# WCS_MK2_v3.net
KiCad netlist of a schematic drawn in EAGLE
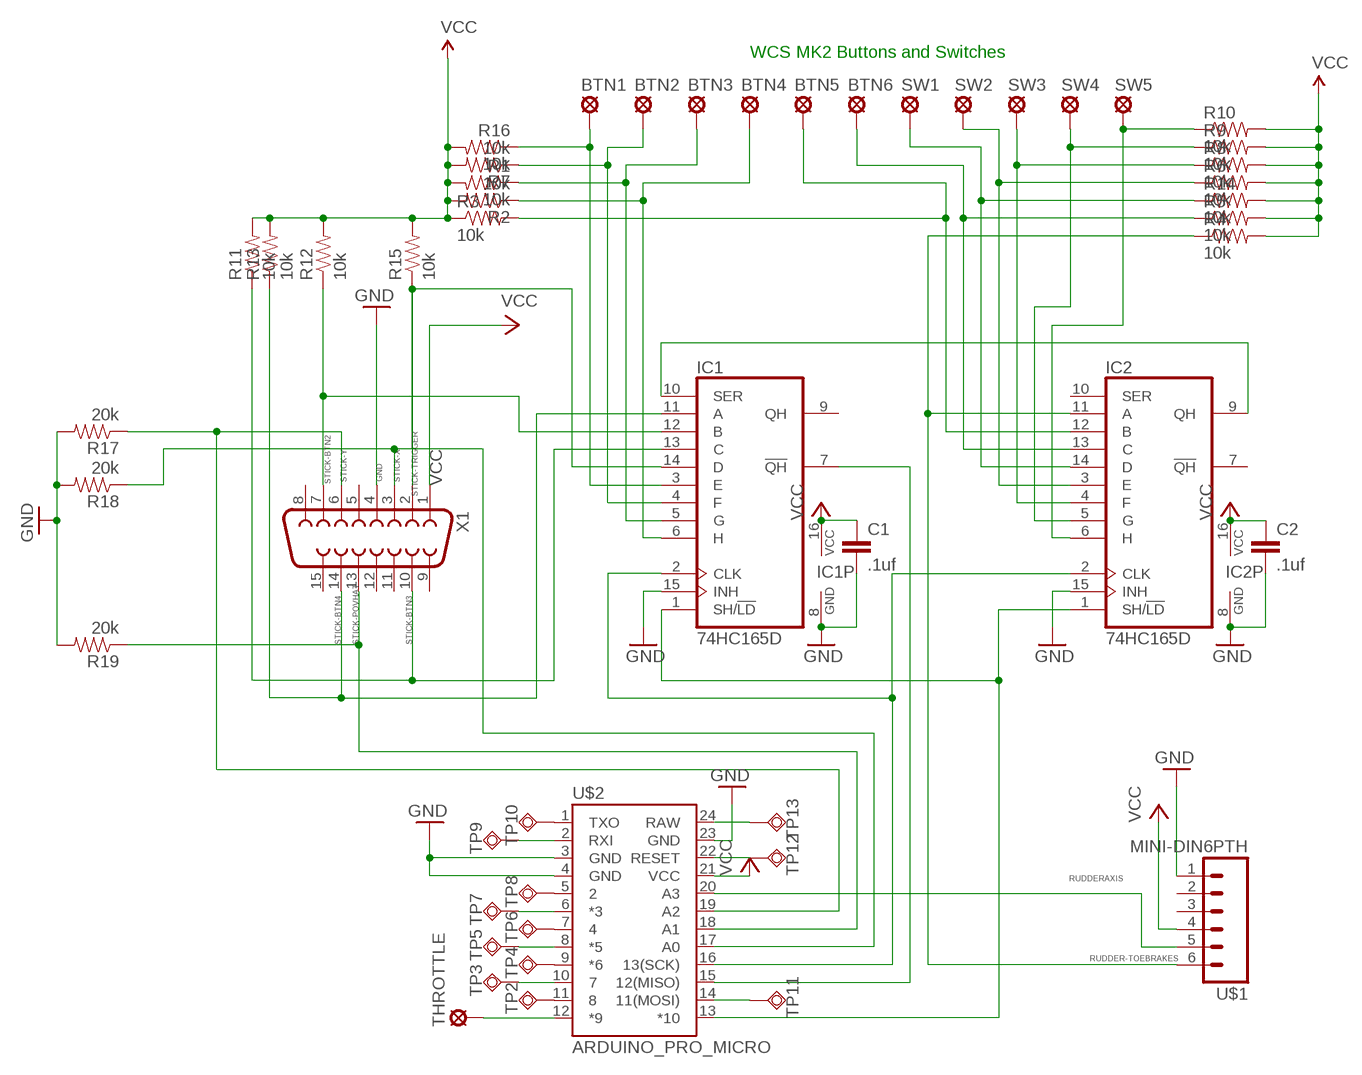
[diagram p0: schematic, sheet 1]

(export (version "E")
  (design (tool "Eeschema 10.0.6"))
  (components
    (comp (ref "BTN1")
      (value "LSP10")
      (footprint "eagle-import:LSP10")
      (libsource (lib "eagle-import") (part "LSP10"))
    )
    (comp (ref "BTN2")
      (value "LSP10")
      (footprint "eagle-import:LSP10")
      (libsource (lib "eagle-import") (part "LSP10"))
    )
    (comp (ref "BTN3")
      (value "LSP10")
      (footprint "eagle-import:LSP10")
      (libsource (lib "eagle-import") (part "LSP10"))
    )
    (comp (ref "BTN4")
      (value "LSP10")
      (footprint "eagle-import:LSP10")
      (libsource (lib "eagle-import") (part "LSP10"))
    )
    (comp (ref "BTN5")
      (value "LSP10")
      (footprint "eagle-import:LSP10")
      (libsource (lib "eagle-import") (part "LSP10"))
    )
    (comp (ref "BTN6")
      (value "LSP10")
      (footprint "eagle-import:LSP10")
      (libsource (lib "eagle-import") (part "LSP10"))
    )
    (comp (ref "C1")
      (value ".1uf")
      (footprint "eagle-import:C025-060X050")
      (libsource (lib "eagle-import") (part "C-EU025-060X050"))
    )
    (comp (ref "C2")
      (value ".1uf")
      (footprint "eagle-import:C025-060X050")
      (libsource (lib "eagle-import") (part "C-EU025-060X050"))
    )
    (comp (ref "IC1")
      (value "74HC165D")
      (footprint "eagle-import:SO16")
      (libsource (lib "eagle-import") (part "74165DHC"))
    )
    (comp (ref "IC2")
      (value "74HC165D")
      (footprint "eagle-import:SO16")
      (libsource (lib "eagle-import") (part "74165DHC"))
    )
    (comp (ref "R1")
      (value "10k")
      (footprint "eagle-import:AXIAL-0.1")
      (libsource (lib "eagle-import") (part "10KOHM-1/4W5%(PTH)VERT"))
    )
    (comp (ref "R2")
      (value "10k")
      (footprint "eagle-import:AXIAL-0.1")
      (libsource (lib "eagle-import") (part "10KOHM-1/4W5%(PTH)VERT"))
    )
    (comp (ref "R3")
      (value "10k")
      (footprint "eagle-import:AXIAL-0.1")
      (libsource (lib "eagle-import") (part "10KOHM-1/4W5%(PTH)VERT"))
    )
    (comp (ref "R4")
      (value "10k")
      (footprint "eagle-import:AXIAL-0.1")
      (libsource (lib "eagle-import") (part "10KOHM-1/4W5%(PTH)VERT"))
    )
    (comp (ref "R5")
      (value "10k")
      (footprint "eagle-import:AXIAL-0.1")
      (libsource (lib "eagle-import") (part "10KOHM-1/4W5%(PTH)VERT"))
    )
    (comp (ref "R6")
      (value "10k")
      (footprint "eagle-import:AXIAL-0.1")
      (libsource (lib "eagle-import") (part "10KOHM-1/4W5%(PTH)VERT"))
    )
    (comp (ref "R7")
      (value "10k")
      (footprint "eagle-import:AXIAL-0.1")
      (libsource (lib "eagle-import") (part "10KOHM-1/4W5%(PTH)VERT"))
    )
    (comp (ref "R8")
      (value "10k")
      (footprint "eagle-import:AXIAL-0.1")
      (libsource (lib "eagle-import") (part "10KOHM-1/4W5%(PTH)VERT"))
    )
    (comp (ref "R9")
      (value "10k")
      (footprint "eagle-import:AXIAL-0.1")
      (libsource (lib "eagle-import") (part "10KOHM-1/4W5%(PTH)VERT"))
    )
    (comp (ref "R10")
      (value "10k")
      (footprint "eagle-import:AXIAL-0.1")
      (libsource (lib "eagle-import") (part "10KOHM-1/4W5%(PTH)VERT"))
    )
    (comp (ref "R11")
      (value "10k")
      (footprint "eagle-import:AXIAL-0.1")
      (libsource (lib "eagle-import") (part "10KOHM-1/4W5%(PTH)VERT"))
    )
    (comp (ref "R12")
      (value "10k")
      (footprint "eagle-import:AXIAL-0.1")
      (libsource (lib "eagle-import") (part "10KOHM-1/4W5%(PTH)VERT"))
    )
    (comp (ref "R13")
      (value "10k")
      (footprint "eagle-import:AXIAL-0.1")
      (libsource (lib "eagle-import") (part "10KOHM-1/4W5%(PTH)VERT"))
    )
    (comp (ref "R14")
      (value "10k")
      (footprint "eagle-import:AXIAL-0.1")
      (libsource (lib "eagle-import") (part "10KOHM-1/4W5%(PTH)VERT"))
    )
    (comp (ref "R15")
      (value "10k")
      (footprint "eagle-import:AXIAL-0.1")
      (libsource (lib "eagle-import") (part "10KOHM-1/4W5%(PTH)VERT"))
    )
    (comp (ref "R16")
      (value "10k")
      (footprint "eagle-import:AXIAL-0.1")
      (libsource (lib "eagle-import") (part "10KOHM-1/4W5%(PTH)VERT"))
    )
    (comp (ref "R17")
      (value "20k")
      (footprint "eagle-import:AXIAL-0.1")
      (libsource (lib "eagle-import") (part "10KOHM-1/4W5%(PTH)VERT"))
    )
    (comp (ref "R18")
      (value "20k")
      (footprint "eagle-import:AXIAL-0.1")
      (libsource (lib "eagle-import") (part "10KOHM-1/4W5%(PTH)VERT"))
    )
    (comp (ref "R19")
      (value "20k")
      (footprint "eagle-import:AXIAL-0.1")
      (libsource (lib "eagle-import") (part "10KOHM-1/4W5%(PTH)VERT"))
    )
    (comp (ref "SW1")
      (value "LSP10")
      (footprint "eagle-import:LSP10")
      (libsource (lib "eagle-import") (part "LSP10"))
    )
    (comp (ref "SW2")
      (value "LSP10")
      (footprint "eagle-import:LSP10")
      (libsource (lib "eagle-import") (part "LSP10"))
    )
    (comp (ref "SW3")
      (value "LSP10")
      (footprint "eagle-import:LSP10")
      (libsource (lib "eagle-import") (part "LSP10"))
    )
    (comp (ref "SW4")
      (value "LSP10")
      (footprint "eagle-import:LSP10")
      (libsource (lib "eagle-import") (part "LSP10"))
    )
    (comp (ref "SW5")
      (value "LSP10")
      (footprint "eagle-import:LSP10")
      (libsource (lib "eagle-import") (part "LSP10"))
    )
    (comp (ref "THROTTLE")
      (value "LSP10")
      (footprint "eagle-import:LSP10")
      (libsource (lib "eagle-import") (part "LSP10"))
    )
    (comp (ref "TP2")
      (value "TPSQTP20SQ")
      (footprint "eagle-import:TP20SQ")
      (libsource (lib "eagle-import") (part "TPSQTP20SQ"))
    )
    (comp (ref "TP3")
      (value "TPSQTP20SQ")
      (footprint "eagle-import:TP20SQ")
      (libsource (lib "eagle-import") (part "TPSQTP20SQ"))
    )
    (comp (ref "TP4")
      (value "TPSQTP20SQ")
      (footprint "eagle-import:TP20SQ")
      (libsource (lib "eagle-import") (part "TPSQTP20SQ"))
    )
    (comp (ref "TP5")
      (value "TPSQTP20SQ")
      (footprint "eagle-import:TP20SQ")
      (libsource (lib "eagle-import") (part "TPSQTP20SQ"))
    )
    (comp (ref "TP6")
      (value "TPSQTP20SQ")
      (footprint "eagle-import:TP20SQ")
      (libsource (lib "eagle-import") (part "TPSQTP20SQ"))
    )
    (comp (ref "TP7")
      (value "TPSQTP20SQ")
      (footprint "eagle-import:TP20SQ")
      (libsource (lib "eagle-import") (part "TPSQTP20SQ"))
    )
    (comp (ref "TP8")
      (value "TPSQTP20SQ")
      (footprint "eagle-import:TP20SQ")
      (libsource (lib "eagle-import") (part "TPSQTP20SQ"))
    )
    (comp (ref "TP9")
      (value "TPSQTP20SQ")
      (footprint "eagle-import:TP20SQ")
      (libsource (lib "eagle-import") (part "TPSQTP20SQ"))
    )
    (comp (ref "TP10")
      (value "TPSQTP20SQ")
      (footprint "eagle-import:TP20SQ")
      (libsource (lib "eagle-import") (part "TPSQTP20SQ"))
    )
    (comp (ref "TP11")
      (value "TPSQTP20SQ")
      (footprint "eagle-import:TP20SQ")
      (libsource (lib "eagle-import") (part "TPSQTP20SQ"))
    )
    (comp (ref "TP12")
      (value "TPSQTP20SQ")
      (footprint "eagle-import:TP20SQ")
      (libsource (lib "eagle-import") (part "TPSQTP20SQ"))
    )
    (comp (ref "TP13")
      (value "TPSQTP20SQ")
      (footprint "eagle-import:TP20SQ")
      (libsource (lib "eagle-import") (part "TPSQTP20SQ"))
    )
    (comp (ref "U$1")
      (value "MINI-DIN6PTH")
      (footprint "eagle-import:MINI-DIN6")
      (libsource (lib "eagle-import") (part "MINI-DIN6PTH"))
    )
    (comp (ref "U$2")
      (value "ARDUINO_PRO_MICRO")
      (footprint "eagle-import:ARDUINO_PRO_MICRO")
      (libsource (lib "eagle-import") (part "ARDUINO_PRO_MICRO"))
    )
    (comp (ref "X1")
      (value "F15HP")
      (footprint "eagle-import:F15HP")
      (libsource (lib "eagle-import") (part "F15HP"))
    )
  )
  (nets
    (net (code "1") (name "/RUDDER-TOEBRAKES") (class "Default")
      (node (ref "IC2") (pin "11") (pinfunction "A_11") (pintype "input"))
      (node (ref "R4") (pin "P$1") (pinfunction "1_P$1") (pintype "passive"))
      (node (ref "U$1") (pin "6") (pinfunction "6_6") (pintype "passive"))
    )
    (net (code "2") (name "/RUDDERAXIS") (class "Default")
      (node (ref "U$1") (pin "5") (pinfunction "5_5") (pintype "passive"))
      (node (ref "U$2") (pin "20") (pinfunction "A3_20") (pintype "bidirectional"))
    )
    (net (code "3") (name "/STICK-BTN2") (class "Default")
      (node (ref "IC1") (pin "12") (pinfunction "B_12") (pintype "input"))
      (node (ref "R12") (pin "P$1") (pinfunction "1_P$1") (pintype "passive"))
      (node (ref "X1") (pin "7") (pinfunction "7_7") (pintype "passive"))
    )
    (net (code "4") (name "/STICK-BTN3") (class "Default")
      (node (ref "IC1") (pin "13") (pinfunction "C_13") (pintype "input"))
      (node (ref "R11") (pin "P$1") (pinfunction "1_P$1") (pintype "passive"))
      (node (ref "X1") (pin "10") (pinfunction "10_10") (pintype "passive"))
    )
    (net (code "5") (name "/STICK-BTN4") (class "Default")
      (node (ref "IC1") (pin "11") (pinfunction "A_11") (pintype "input"))
      (node (ref "R13") (pin "P$1") (pinfunction "1_P$1") (pintype "passive"))
      (node (ref "X1") (pin "14") (pinfunction "14_14") (pintype "passive"))
    )
    (net (code "6") (name "/STICK-POVHAT") (class "Default")
      (node (ref "R19") (pin "P$1") (pinfunction "1_P$1") (pintype "passive"))
      (node (ref "U$2") (pin "18") (pinfunction "A1_18") (pintype "bidirectional"))
      (node (ref "X1") (pin "13") (pinfunction "13_13") (pintype "passive"))
    )
    (net (code "7") (name "/STICK-TRIGGER") (class "Default")
      (node (ref "IC1") (pin "14") (pinfunction "D_14") (pintype "input"))
      (node (ref "R15") (pin "P$1") (pinfunction "1_P$1") (pintype "passive"))
      (node (ref "X1") (pin "2") (pinfunction "2_2") (pintype "passive"))
    )
    (net (code "8") (name "/STICK-X") (class "Default")
      (node (ref "R18") (pin "P$1") (pinfunction "1_P$1") (pintype "passive"))
      (node (ref "U$2") (pin "17") (pinfunction "A0_17") (pintype "bidirectional"))
      (node (ref "X1") (pin "3") (pinfunction "3_3") (pintype "passive"))
    )
    (net (code "9") (name "/STICK-Y") (class "Default")
      (node (ref "R17") (pin "P$1") (pinfunction "1_P$1") (pintype "passive"))
      (node (ref "U$2") (pin "19") (pinfunction "A2_19") (pintype "bidirectional"))
      (node (ref "X1") (pin "6") (pinfunction "6_6") (pintype "passive"))
    )
    (net (code "10") (name "GND") (class "Default")
      (node (ref "C1") (pin "2") (pinfunction "2_2") (pintype "passive"))
      (node (ref "C2") (pin "2") (pinfunction "2_2") (pintype "passive"))
      (node (ref "IC1") (pin "15") (pinfunction "INH_15") (pintype "input"))
      (node (ref "IC1") (pin "8") (pinfunction "GND_8") (pintype "power_in"))
      (node (ref "IC2") (pin "15") (pinfunction "INH_15") (pintype "input"))
      (node (ref "IC2") (pin "8") (pinfunction "GND_8") (pintype "power_in"))
      (node (ref "R17") (pin "P$2") (pinfunction "2_P$2") (pintype "passive"))
      (node (ref "R18") (pin "P$2") (pinfunction "2_P$2") (pintype "passive"))
      (node (ref "R19") (pin "P$2") (pinfunction "2_P$2") (pintype "passive"))
      (node (ref "U$1") (pin "1") (pinfunction "1_1") (pintype "passive"))
      (node (ref "U$2") (pin "23") (pinfunction "GND_23") (pintype "bidirectional"))
      (node (ref "U$2") (pin "3") (pinfunction "GND_3") (pintype "bidirectional"))
      (node (ref "U$2") (pin "4") (pinfunction "GND_4") (pintype "bidirectional"))
      (node (ref "X1") (pin "4") (pinfunction "4_4") (pintype "passive"))
    )
    (net (code "11") (name "Net-(IC1A-CLK)") (class "Default")
      (node (ref "IC1") (pin "2") (pinfunction "CLK_2") (pintype "input"))
      (node (ref "IC2") (pin "2") (pinfunction "CLK_2") (pintype "input"))
      (node (ref "U$2") (pin "16") (pinfunction "13(SCK)_16") (pintype "bidirectional"))
    )
    (net (code "12") (name "Net-(IC1A-E)") (class "Default")
      (node (ref "BTN1") (pin "MP") (pinfunction "MP_MP") (pintype "passive"))
      (node (ref "IC1") (pin "3") (pinfunction "E_3") (pintype "input"))
      (node (ref "R16") (pin "P$1") (pinfunction "1_P$1") (pintype "passive"))
    )
    (net (code "13") (name "Net-(IC1A-F)") (class "Default")
      (node (ref "BTN2") (pin "MP") (pinfunction "MP_MP") (pintype "passive"))
      (node (ref "IC1") (pin "4") (pinfunction "F_4") (pintype "input"))
      (node (ref "R7") (pin "P$1") (pinfunction "1_P$1") (pintype "passive"))
    )
    (net (code "14") (name "Net-(IC1A-G)") (class "Default")
      (node (ref "BTN3") (pin "MP") (pinfunction "MP_MP") (pintype "passive"))
      (node (ref "IC1") (pin "5") (pinfunction "G_5") (pintype "input"))
      (node (ref "R1") (pin "P$1") (pinfunction "1_P$1") (pintype "passive"))
    )
    (net (code "15") (name "Net-(IC1A-H)") (class "Default")
      (node (ref "BTN4") (pin "MP") (pinfunction "MP_MP") (pintype "passive"))
      (node (ref "IC1") (pin "6") (pinfunction "H_6") (pintype "input"))
      (node (ref "R2") (pin "P$1") (pinfunction "1_P$1") (pintype "passive"))
    )
    (net (code "16") (name "Net-(IC1A-SER)") (class "Default")
      (node (ref "IC1") (pin "10") (pinfunction "SER_10") (pintype "input"))
      (node (ref "IC2") (pin "9") (pinfunction "QH_9") (pintype "output"))
    )
    (net (code "17") (name "Net-(IC1A-SH{slash}~{LD})") (class "Default")
      (node (ref "IC1") (pin "1") (pinfunction "SH/~{LD}_1") (pintype "input"))
      (node (ref "IC2") (pin "1") (pinfunction "SH/~{LD}_1") (pintype "input"))
      (node (ref "U$2") (pin "13") (pinfunction "*10_13") (pintype "bidirectional"))
    )
    (net (code "18") (name "Net-(IC1A-~{QH})") (class "Default")
      (node (ref "IC1") (pin "7") (pinfunction "~{QH}_7") (pintype "output"))
      (node (ref "U$2") (pin "15") (pinfunction "12(MISO)_15") (pintype "bidirectional"))
    )
    (net (code "19") (name "Net-(IC2A-B)") (class "Default")
      (node (ref "BTN5") (pin "MP") (pinfunction "MP_MP") (pintype "passive"))
      (node (ref "IC2") (pin "12") (pinfunction "B_12") (pintype "input"))
      (node (ref "R3") (pin "P$2") (pinfunction "2_P$2") (pintype "passive"))
    )
    (net (code "20") (name "Net-(IC2A-C)") (class "Default")
      (node (ref "BTN6") (pin "MP") (pinfunction "MP_MP") (pintype "passive"))
      (node (ref "IC2") (pin "13") (pinfunction "C_13") (pintype "input"))
      (node (ref "R5") (pin "P$1") (pinfunction "1_P$1") (pintype "passive"))
    )
    (net (code "21") (name "Net-(IC2A-D)") (class "Default")
      (node (ref "IC2") (pin "14") (pinfunction "D_14") (pintype "input"))
      (node (ref "R14") (pin "P$1") (pinfunction "1_P$1") (pintype "passive"))
      (node (ref "SW1") (pin "MP") (pinfunction "MP_MP") (pintype "passive"))
    )
    (net (code "22") (name "Net-(IC2A-E)") (class "Default")
      (node (ref "IC2") (pin "3") (pinfunction "E_3") (pintype "input"))
      (node (ref "R6") (pin "P$1") (pinfunction "1_P$1") (pintype "passive"))
      (node (ref "SW2") (pin "MP") (pinfunction "MP_MP") (pintype "passive"))
    )
    (net (code "23") (name "Net-(IC2A-F)") (class "Default")
      (node (ref "IC2") (pin "4") (pinfunction "F_4") (pintype "input"))
      (node (ref "R8") (pin "P$1") (pinfunction "1_P$1") (pintype "passive"))
      (node (ref "SW3") (pin "MP") (pinfunction "MP_MP") (pintype "passive"))
    )
    (net (code "24") (name "Net-(IC2A-G)") (class "Default")
      (node (ref "IC2") (pin "5") (pinfunction "G_5") (pintype "input"))
      (node (ref "R9") (pin "P$1") (pinfunction "1_P$1") (pintype "passive"))
      (node (ref "SW4") (pin "MP") (pinfunction "MP_MP") (pintype "passive"))
    )
    (net (code "25") (name "Net-(IC2A-H)") (class "Default")
      (node (ref "IC2") (pin "6") (pinfunction "H_6") (pintype "input"))
      (node (ref "R10") (pin "P$1") (pinfunction "1_P$1") (pintype "passive"))
      (node (ref "SW5") (pin "MP") (pinfunction "MP_MP") (pintype "passive"))
    )
    (net (code "26") (name "Net-(U$2-*3)") (class "Default")
      (node (ref "TP7") (pin "TP") (pinfunction "TP_TP") (pintype "input"))
      (node (ref "U$2") (pin "6") (pinfunction "*3_6") (pintype "bidirectional"))
    )
    (net (code "27") (name "Net-(U$2-*5)") (class "Default")
      (node (ref "TP5") (pin "TP") (pinfunction "TP_TP") (pintype "input"))
      (node (ref "U$2") (pin "8") (pinfunction "*5_8") (pintype "bidirectional"))
    )
    (net (code "28") (name "Net-(U$2-*6)") (class "Default")
      (node (ref "TP4") (pin "TP") (pinfunction "TP_TP") (pintype "input"))
      (node (ref "U$2") (pin "9") (pinfunction "*6_9") (pintype "bidirectional"))
    )
    (net (code "29") (name "Net-(U$2-*9)") (class "Default")
      (node (ref "THROTTLE") (pin "MP") (pinfunction "MP_MP") (pintype "passive"))
      (node (ref "U$2") (pin "12") (pinfunction "*9_12") (pintype "bidirectional"))
    )
    (net (code "30") (name "Net-(U$2-2)") (class "Default")
      (node (ref "TP8") (pin "TP") (pinfunction "TP_TP") (pintype "input"))
      (node (ref "U$2") (pin "5") (pinfunction "2_5") (pintype "bidirectional"))
    )
    (net (code "31") (name "Net-(U$2-4)") (class "Default")
      (node (ref "TP6") (pin "TP") (pinfunction "TP_TP") (pintype "input"))
      (node (ref "U$2") (pin "7") (pinfunction "4_7") (pintype "bidirectional"))
    )
    (net (code "32") (name "Net-(U$2-7)") (class "Default")
      (node (ref "TP3") (pin "TP") (pinfunction "TP_TP") (pintype "input"))
      (node (ref "U$2") (pin "10") (pinfunction "7_10") (pintype "bidirectional"))
    )
    (net (code "33") (name "Net-(U$2-8)") (class "Default")
      (node (ref "TP2") (pin "TP") (pinfunction "TP_TP") (pintype "input"))
      (node (ref "U$2") (pin "11") (pinfunction "8_11") (pintype "bidirectional"))
    )
    (net (code "34") (name "Net-(U$2-11(MOSI))") (class "Default")
      (node (ref "TP11") (pin "TP") (pinfunction "TP_TP") (pintype "input"))
      (node (ref "U$2") (pin "14") (pinfunction "11(MOSI)_14") (pintype "bidirectional"))
    )
    (net (code "35") (name "Net-(U$2-RAW)") (class "Default")
      (node (ref "TP13") (pin "TP") (pinfunction "TP_TP") (pintype "input"))
      (node (ref "U$2") (pin "24") (pinfunction "RAW_24") (pintype "bidirectional"))
    )
    (net (code "36") (name "Net-(U$2-RESET)") (class "Default")
      (node (ref "TP12") (pin "TP") (pinfunction "TP_TP") (pintype "input"))
      (node (ref "U$2") (pin "22") (pinfunction "RESET_22") (pintype "bidirectional"))
    )
    (net (code "37") (name "Net-(U$2-RXI)") (class "Default")
      (node (ref "TP9") (pin "TP") (pinfunction "TP_TP") (pintype "input"))
      (node (ref "U$2") (pin "2") (pinfunction "RXI_2") (pintype "bidirectional"))
    )
    (net (code "38") (name "Net-(U$2-TXO)") (class "Default")
      (node (ref "TP10") (pin "TP") (pinfunction "TP_TP") (pintype "input"))
      (node (ref "U$2") (pin "1") (pinfunction "TXO_1") (pintype "bidirectional"))
    )
    (net (code "39") (name "VCC") (class "Default")
      (node (ref "C1") (pin "1") (pinfunction "1_1") (pintype "passive"))
      (node (ref "C2") (pin "1") (pinfunction "1_1") (pintype "passive"))
      (node (ref "IC1") (pin "16") (pinfunction "VCC_16") (pintype "power_in"))
      (node (ref "IC2") (pin "16") (pinfunction "VCC_16") (pintype "power_in"))
      (node (ref "R1") (pin "P$2") (pinfunction "2_P$2") (pintype "passive"))
      (node (ref "R10") (pin "P$2") (pinfunction "2_P$2") (pintype "passive"))
      (node (ref "R11") (pin "P$2") (pinfunction "2_P$2") (pintype "passive"))
      (node (ref "R12") (pin "P$2") (pinfunction "2_P$2") (pintype "passive"))
      (node (ref "R13") (pin "P$2") (pinfunction "2_P$2") (pintype "passive"))
      (node (ref "R14") (pin "P$2") (pinfunction "2_P$2") (pintype "passive"))
      (node (ref "R15") (pin "P$2") (pinfunction "2_P$2") (pintype "passive"))
      (node (ref "R16") (pin "P$2") (pinfunction "2_P$2") (pintype "passive"))
      (node (ref "R2") (pin "P$2") (pinfunction "2_P$2") (pintype "passive"))
      (node (ref "R3") (pin "P$1") (pinfunction "1_P$1") (pintype "passive"))
      (node (ref "R4") (pin "P$2") (pinfunction "2_P$2") (pintype "passive"))
      (node (ref "R5") (pin "P$2") (pinfunction "2_P$2") (pintype "passive"))
      (node (ref "R6") (pin "P$2") (pinfunction "2_P$2") (pintype "passive"))
      (node (ref "R7") (pin "P$2") (pinfunction "2_P$2") (pintype "passive"))
      (node (ref "R8") (pin "P$2") (pinfunction "2_P$2") (pintype "passive"))
      (node (ref "R9") (pin "P$2") (pinfunction "2_P$2") (pintype "passive"))
      (node (ref "U$1") (pin "4") (pinfunction "4_4") (pintype "passive"))
      (node (ref "U$2") (pin "21") (pinfunction "VCC_21") (pintype "bidirectional"))
      (node (ref "X1") (pin "1") (pinfunction "1_1") (pintype "passive"))
    )
    (net (code "40") (name "unconnected-(IC1A-QH-Pad9)") (class "Default")
      (node (ref "IC1") (pin "9") (pinfunction "QH_9") (pintype "output"))
    )
    (net (code "41") (name "unconnected-(IC2A-SER-Pad10)") (class "Default")
      (node (ref "IC2") (pin "10") (pinfunction "SER_10") (pintype "input"))
    )
    (net (code "42") (name "unconnected-(IC2A-~{QH}-Pad7)") (class "Default")
      (node (ref "IC2") (pin "7") (pinfunction "~{QH}_7") (pintype "output"))
    )
    (net (code "43") (name "unconnected-(U$1-Pad2)") (class "Default")
      (node (ref "U$1") (pin "2") (pinfunction "2_2") (pintype "passive"))
    )
    (net (code "44") (name "unconnected-(U$1-Pad3)") (class "Default")
      (node (ref "U$1") (pin "3") (pinfunction "3_3") (pintype "passive"))
    )
    (net (code "45") (name "unconnected-(X1-Pad5)") (class "Default")
      (node (ref "X1") (pin "5") (pinfunction "5_5") (pintype "passive"))
    )
    (net (code "46") (name "unconnected-(X1-Pad8)") (class "Default")
      (node (ref "X1") (pin "8") (pinfunction "8_8") (pintype "passive"))
    )
    (net (code "47") (name "unconnected-(X1-Pad9)") (class "Default")
      (node (ref "X1") (pin "9") (pinfunction "9_9") (pintype "passive"))
    )
    (net (code "48") (name "unconnected-(X1-Pad11)") (class "Default")
      (node (ref "X1") (pin "11") (pinfunction "11_11") (pintype "passive"))
    )
    (net (code "49") (name "unconnected-(X1-Pad12)") (class "Default")
      (node (ref "X1") (pin "12") (pinfunction "12_12") (pintype "passive"))
    )
    (net (code "50") (name "unconnected-(X1-Pad15)") (class "Default")
      (node (ref "X1") (pin "15") (pinfunction "15_15") (pintype "passive"))
    )
  )
)
